# Phaser_2.net
KiCad netlist of a schematic drawn in Altium Designer
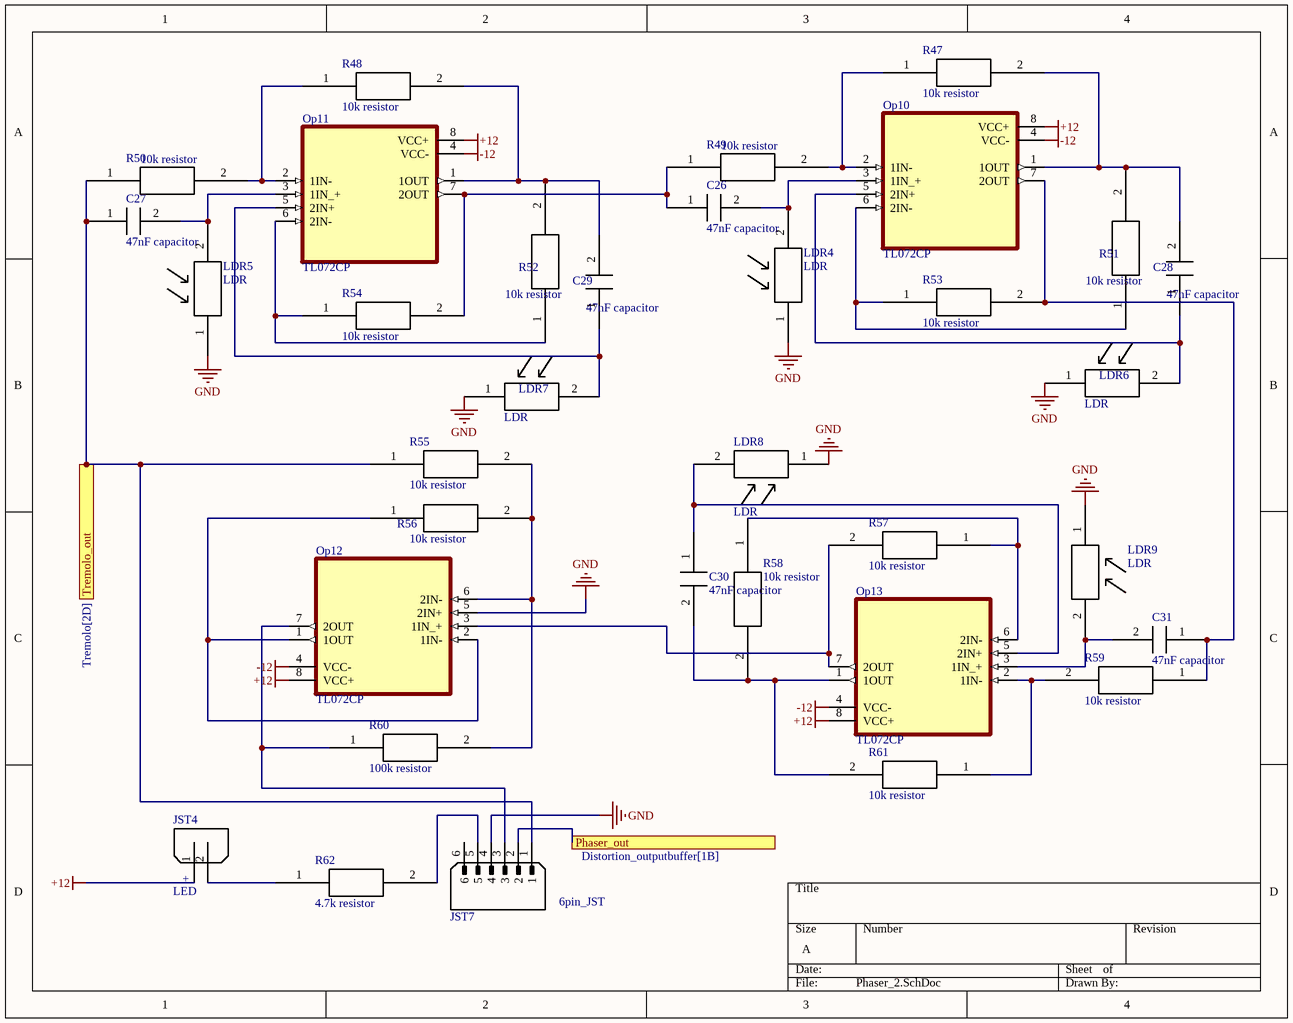
[diagram p0: Phaser_2.SchDoc]

(export (version "E")
  (design (tool "Eeschema 10.0.6"))
  (components
    (comp (ref "C26")
      (value "47nF capacitor")
      (footprint "47nF")
      (libsource (lib "Analog_Project_Schlib") (part "47nF capacitor"))
    )
    (comp (ref "C27")
      (value "47nF capacitor")
      (footprint "47nF")
      (libsource (lib "Analog_Project_Schlib") (part "47nF capacitor"))
    )
    (comp (ref "C28")
      (value "47nF capacitor")
      (footprint "47nF")
      (libsource (lib "Analog_Project_Schlib") (part "47nF capacitor"))
    )
    (comp (ref "C29")
      (value "47nF capacitor")
      (footprint "47nF")
      (libsource (lib "Analog_Project_Schlib") (part "47nF capacitor"))
    )
    (comp (ref "C30")
      (value "47nF capacitor")
      (footprint "47nF")
      (libsource (lib "Analog_Project_Schlib") (part "47nF capacitor"))
    )
    (comp (ref "C31")
      (value "47nF capacitor")
      (footprint "47nF")
      (libsource (lib "Analog_Project_Schlib") (part "47nF capacitor"))
    )
    (comp (ref "JST4")
      (value "LED")
      (footprint "2pin_JST")
      (libsource (lib "Analog_Project_Schlib") (part "2pin_JST"))
    )
    (comp (ref "JST7")
      (value "6pin_JST")
      (footprint "6pin_JST")
      (libsource (lib "Analog_Project_Schlib") (part "6pin_JST"))
    )
    (comp (ref "LDR4") (value "LDR") (footprint "LDR") (libsource (lib "Analog_Project_Schlib") (part "LDR")))
    (comp (ref "LDR5") (value "LDR") (footprint "LDR") (libsource (lib "Analog_Project_Schlib") (part "LDR")))
    (comp (ref "LDR6") (value "LDR") (footprint "LDR") (libsource (lib "Analog_Project_Schlib") (part "LDR")))
    (comp (ref "LDR7") (value "LDR") (footprint "LDR") (libsource (lib "Analog_Project_Schlib") (part "LDR")))
    (comp (ref "LDR8") (value "LDR") (footprint "LDR") (libsource (lib "Analog_Project_Schlib") (part "LDR")))
    (comp (ref "LDR9") (value "LDR") (footprint "LDR") (libsource (lib "Analog_Project_Schlib") (part "LDR")))
    (comp (ref "Op10")
      (value "TL072CP")
      (footprint "TL072CP")
      (libsource (lib "Analog_Project_Schlib") (part "TL072CP"))
    )
    (comp (ref "Op11")
      (value "TL072CP")
      (footprint "TL072CP")
      (libsource (lib "Analog_Project_Schlib") (part "TL072CP"))
    )
    (comp (ref "Op12") (value "TL072CP") (footprint "TL072CP") (libsource (lib "") (part "TL072CP_1")))
    (comp (ref "Op13") (value "TL072CP") (footprint "TL072CP") (libsource (lib "") (part "TL072CP_1")))
    (comp (ref "R47")
      (value "10k resistor")
      (footprint "10k")
      (libsource (lib "Analog_Project_Schlib") (part "10k resistor"))
    )
    (comp (ref "R48")
      (value "10k resistor")
      (footprint "10k")
      (libsource (lib "Analog_Project_Schlib") (part "10k resistor"))
    )
    (comp (ref "R49")
      (value "10k resistor")
      (footprint "10k")
      (libsource (lib "Analog_Project_Schlib") (part "10k resistor"))
    )
    (comp (ref "R50")
      (value "10k resistor")
      (footprint "10k")
      (libsource (lib "Analog_Project_Schlib") (part "10k resistor"))
    )
    (comp (ref "R51")
      (value "10k resistor")
      (footprint "10k")
      (libsource (lib "Analog_Project_Schlib") (part "10k resistor"))
    )
    (comp (ref "R52")
      (value "10k resistor")
      (footprint "10k")
      (libsource (lib "Analog_Project_Schlib") (part "10k resistor"))
    )
    (comp (ref "R53")
      (value "10k resistor")
      (footprint "10k")
      (libsource (lib "Analog_Project_Schlib") (part "10k resistor"))
    )
    (comp (ref "R54")
      (value "10k resistor")
      (footprint "10k")
      (libsource (lib "Analog_Project_Schlib") (part "10k resistor"))
    )
    (comp (ref "R55")
      (value "10k resistor")
      (footprint "10k")
      (libsource (lib "Analog_Project_Schlib") (part "10k resistor"))
    )
    (comp (ref "R56")
      (value "10k resistor")
      (footprint "10k")
      (libsource (lib "Analog_Project_Schlib") (part "10k resistor"))
    )
    (comp (ref "R57")
      (value "10k resistor")
      (footprint "10k")
      (libsource (lib "Analog_Project_Schlib") (part "10k resistor"))
    )
    (comp (ref "R58")
      (value "10k resistor")
      (footprint "10k")
      (libsource (lib "Analog_Project_Schlib") (part "10k resistor"))
    )
    (comp (ref "R59")
      (value "10k resistor")
      (footprint "10k")
      (libsource (lib "Analog_Project_Schlib") (part "10k resistor"))
    )
    (comp (ref "R60")
      (value "100k resistor")
      (footprint "100k")
      (libsource (lib "Analog_Project_Schlib") (part "100k resistor"))
    )
    (comp (ref "R61")
      (value "10k resistor")
      (footprint "10k")
      (libsource (lib "Analog_Project_Schlib") (part "10k resistor"))
    )
    (comp (ref "R62")
      (value "4.7k resistor")
      (footprint "4.7k")
      (libsource (lib "Analog_Project_Schlib") (part "4.7k resistor"))
    )
  )
  (nets
    (net (code "1") (name "+12") (class "Default")
      (node (ref "JST4") (pin "1") (pinfunction "1_1") (pintype "passive"))
      (node (ref "Op10") (pin "8") (pinfunction "VCC+_8") (pintype "power_in"))
      (node (ref "Op11") (pin "8") (pinfunction "VCC+_8") (pintype "power_in"))
      (node (ref "Op12") (pin "8") (pinfunction "VCC+_8") (pintype "power_in"))
      (node (ref "Op13") (pin "8") (pinfunction "VCC+_8") (pintype "power_in"))
    )
    (net (code "2") (name "-12") (class "Default")
      (node (ref "Op10") (pin "4") (pinfunction "VCC-_4") (pintype "power_in"))
      (node (ref "Op11") (pin "4") (pinfunction "VCC-_4") (pintype "power_in"))
      (node (ref "Op12") (pin "4") (pinfunction "VCC-_4") (pintype "power_in"))
      (node (ref "Op13") (pin "4") (pinfunction "VCC-_4") (pintype "power_in"))
    )
    (net (code "3") (name "/Phaser_out") (class "Default")
      (node (ref "JST7") (pin "2") (pinfunction "2_2") (pintype "passive"))
    )
    (net (code "4") (name "/Tremolo_out") (class "Default")
      (node (ref "C27") (pin "1") (pinfunction "1_1") (pintype "passive"))
      (node (ref "JST7") (pin "1") (pinfunction "1_1") (pintype "passive"))
      (node (ref "R50") (pin "1") (pinfunction "1_1") (pintype "passive"))
      (node (ref "R55") (pin "1") (pinfunction "1_1") (pintype "passive"))
    )
    (net (code "5") (name "GND") (class "Default")
      (node (ref "JST7") (pin "4") (pinfunction "4_4") (pintype "passive"))
      (node (ref "LDR4") (pin "1") (pinfunction "1_1") (pintype "passive"))
      (node (ref "LDR5") (pin "1") (pinfunction "1_1") (pintype "passive"))
      (node (ref "LDR6") (pin "1") (pinfunction "1_1") (pintype "passive"))
      (node (ref "LDR7") (pin "1") (pinfunction "1_1") (pintype "passive"))
      (node (ref "LDR8") (pin "1") (pinfunction "1_1") (pintype "passive"))
      (node (ref "LDR9") (pin "1") (pinfunction "1_1") (pintype "passive"))
      (node (ref "Op12") (pin "5") (pinfunction "2IN+_5") (pintype "input"))
    )
    (net (code "6") (name "Net-(JST4-Pad2)") (class "Default")
      (node (ref "JST4") (pin "2") (pinfunction "2_2") (pintype "passive"))
      (node (ref "R62") (pin "1") (pinfunction "1_1") (pintype "passive"))
    )
    (net (code "7") (name "Net-(JST7-Pad5)") (class "Default")
      (node (ref "JST7") (pin "5") (pinfunction "5_5") (pintype "passive"))
      (node (ref "R62") (pin "2") (pinfunction "2_2") (pintype "passive"))
    )
    (net (code "8") (name "Net-(Op10-1IN-)") (class "Default")
      (node (ref "Op10") (pin "2") (pinfunction "1IN-_2") (pintype "input"))
      (node (ref "R47") (pin "1") (pinfunction "1_1") (pintype "passive"))
      (node (ref "R49") (pin "2") (pinfunction "2_2") (pintype "passive"))
    )
    (net (code "9") (name "Net-(Op10-1IN_+)") (class "Default")
      (node (ref "C26") (pin "2") (pinfunction "2_2") (pintype "passive"))
      (node (ref "LDR4") (pin "2") (pinfunction "2_2") (pintype "passive"))
      (node (ref "Op10") (pin "3") (pinfunction "1IN_+_3") (pintype "input"))
    )
    (net (code "10") (name "Net-(Op10-1OUT)") (class "Default")
      (node (ref "C28") (pin "2") (pinfunction "2_2") (pintype "passive"))
      (node (ref "Op10") (pin "1") (pinfunction "1OUT_1") (pintype "output"))
      (node (ref "R47") (pin "2") (pinfunction "2_2") (pintype "passive"))
      (node (ref "R51") (pin "2") (pinfunction "2_2") (pintype "passive"))
    )
    (net (code "11") (name "Net-(Op10-2IN+)") (class "Default")
      (node (ref "C28") (pin "1") (pinfunction "1_1") (pintype "passive"))
      (node (ref "LDR6") (pin "2") (pinfunction "2_2") (pintype "passive"))
      (node (ref "Op10") (pin "5") (pinfunction "2IN+_5") (pintype "input"))
    )
    (net (code "12") (name "Net-(Op10-2IN-)") (class "Default")
      (node (ref "Op10") (pin "6") (pinfunction "2IN-_6") (pintype "input"))
      (node (ref "R51") (pin "1") (pinfunction "1_1") (pintype "passive"))
      (node (ref "R53") (pin "1") (pinfunction "1_1") (pintype "passive"))
    )
    (net (code "13") (name "Net-(Op10-2OUT)") (class "Default")
      (node (ref "C31") (pin "1") (pinfunction "1_1") (pintype "passive"))
      (node (ref "Op10") (pin "7") (pinfunction "2OUT_7") (pintype "output"))
      (node (ref "R53") (pin "2") (pinfunction "2_2") (pintype "passive"))
      (node (ref "R59") (pin "1") (pinfunction "1_1") (pintype "passive"))
    )
    (net (code "14") (name "Net-(Op11-1IN-)") (class "Default")
      (node (ref "Op11") (pin "2") (pinfunction "1IN-_2") (pintype "input"))
      (node (ref "R48") (pin "1") (pinfunction "1_1") (pintype "passive"))
      (node (ref "R50") (pin "2") (pinfunction "2_2") (pintype "passive"))
    )
    (net (code "15") (name "Net-(Op11-1IN_+)") (class "Default")
      (node (ref "C27") (pin "2") (pinfunction "2_2") (pintype "passive"))
      (node (ref "LDR5") (pin "2") (pinfunction "2_2") (pintype "passive"))
      (node (ref "Op11") (pin "3") (pinfunction "1IN_+_3") (pintype "input"))
    )
    (net (code "16") (name "Net-(Op11-1OUT)") (class "Default")
      (node (ref "C29") (pin "2") (pinfunction "2_2") (pintype "passive"))
      (node (ref "Op11") (pin "1") (pinfunction "1OUT_1") (pintype "output"))
      (node (ref "R48") (pin "2") (pinfunction "2_2") (pintype "passive"))
      (node (ref "R52") (pin "2") (pinfunction "2_2") (pintype "passive"))
    )
    (net (code "17") (name "Net-(Op11-2IN+)") (class "Default")
      (node (ref "C29") (pin "1") (pinfunction "1_1") (pintype "passive"))
      (node (ref "LDR7") (pin "2") (pinfunction "2_2") (pintype "passive"))
      (node (ref "Op11") (pin "5") (pinfunction "2IN+_5") (pintype "input"))
    )
    (net (code "18") (name "Net-(Op11-2IN-)") (class "Default")
      (node (ref "Op11") (pin "6") (pinfunction "2IN-_6") (pintype "input"))
      (node (ref "R52") (pin "1") (pinfunction "1_1") (pintype "passive"))
      (node (ref "R54") (pin "1") (pinfunction "1_1") (pintype "passive"))
    )
    (net (code "19") (name "Net-(Op11-2OUT)") (class "Default")
      (node (ref "C26") (pin "1") (pinfunction "1_1") (pintype "passive"))
      (node (ref "Op11") (pin "7") (pinfunction "2OUT_7") (pintype "output"))
      (node (ref "R49") (pin "1") (pinfunction "1_1") (pintype "passive"))
      (node (ref "R54") (pin "2") (pinfunction "2_2") (pintype "passive"))
    )
    (net (code "20") (name "Net-(Op12-1IN-)") (class "Default")
      (node (ref "Op12") (pin "1") (pinfunction "1OUT_1") (pintype "output"))
      (node (ref "Op12") (pin "2") (pinfunction "1IN-_2") (pintype "input"))
      (node (ref "R56") (pin "1") (pinfunction "1_1") (pintype "passive"))
    )
    (net (code "21") (name "Net-(Op12-1IN_+)") (class "Default")
      (node (ref "Op12") (pin "3") (pinfunction "1IN_+_3") (pintype "input"))
      (node (ref "Op13") (pin "7") (pinfunction "2OUT_7") (pintype "output"))
      (node (ref "R57") (pin "2") (pinfunction "2_2") (pintype "passive"))
    )
    (net (code "22") (name "Net-(Op12-2IN-)") (class "Default")
      (node (ref "Op12") (pin "6") (pinfunction "2IN-_6") (pintype "input"))
      (node (ref "R55") (pin "2") (pinfunction "2_2") (pintype "passive"))
      (node (ref "R56") (pin "2") (pinfunction "2_2") (pintype "passive"))
      (node (ref "R60") (pin "2") (pinfunction "2_2") (pintype "passive"))
    )
    (net (code "23") (name "Net-(Op12-2OUT)") (class "Default")
      (node (ref "JST7") (pin "3") (pinfunction "3_3") (pintype "passive"))
      (node (ref "Op12") (pin "7") (pinfunction "2OUT_7") (pintype "output"))
      (node (ref "R60") (pin "1") (pinfunction "1_1") (pintype "passive"))
    )
    (net (code "24") (name "Net-(Op13-1IN-)") (class "Default")
      (node (ref "Op13") (pin "2") (pinfunction "1IN-_2") (pintype "input"))
      (node (ref "R59") (pin "2") (pinfunction "2_2") (pintype "passive"))
      (node (ref "R61") (pin "1") (pinfunction "1_1") (pintype "passive"))
    )
    (net (code "25") (name "Net-(Op13-1IN_+)") (class "Default")
      (node (ref "C31") (pin "2") (pinfunction "2_2") (pintype "passive"))
      (node (ref "LDR9") (pin "2") (pinfunction "2_2") (pintype "passive"))
      (node (ref "Op13") (pin "3") (pinfunction "1IN_+_3") (pintype "input"))
    )
    (net (code "26") (name "Net-(Op13-1OUT)") (class "Default")
      (node (ref "C30") (pin "2") (pinfunction "2_2") (pintype "passive"))
      (node (ref "Op13") (pin "1") (pinfunction "1OUT_1") (pintype "output"))
      (node (ref "R58") (pin "2") (pinfunction "2_2") (pintype "passive"))
      (node (ref "R61") (pin "2") (pinfunction "2_2") (pintype "passive"))
    )
    (net (code "27") (name "Net-(Op13-2IN+)") (class "Default")
      (node (ref "C30") (pin "1") (pinfunction "1_1") (pintype "passive"))
      (node (ref "LDR8") (pin "2") (pinfunction "2_2") (pintype "passive"))
      (node (ref "Op13") (pin "5") (pinfunction "2IN+_5") (pintype "input"))
    )
    (net (code "28") (name "Net-(Op13-2IN-)") (class "Default")
      (node (ref "Op13") (pin "6") (pinfunction "2IN-_6") (pintype "input"))
      (node (ref "R57") (pin "1") (pinfunction "1_1") (pintype "passive"))
      (node (ref "R58") (pin "1") (pinfunction "1_1") (pintype "passive"))
    )
    (net (code "29") (name "unconnected-(JST7-Pad6)") (class "Default")
      (node (ref "JST7") (pin "6") (pinfunction "6_6") (pintype "passive"))
    )
  )
)
